# USR_IO_IPMI.net
KiCad netlist of a schematic drawn in Altium Designer
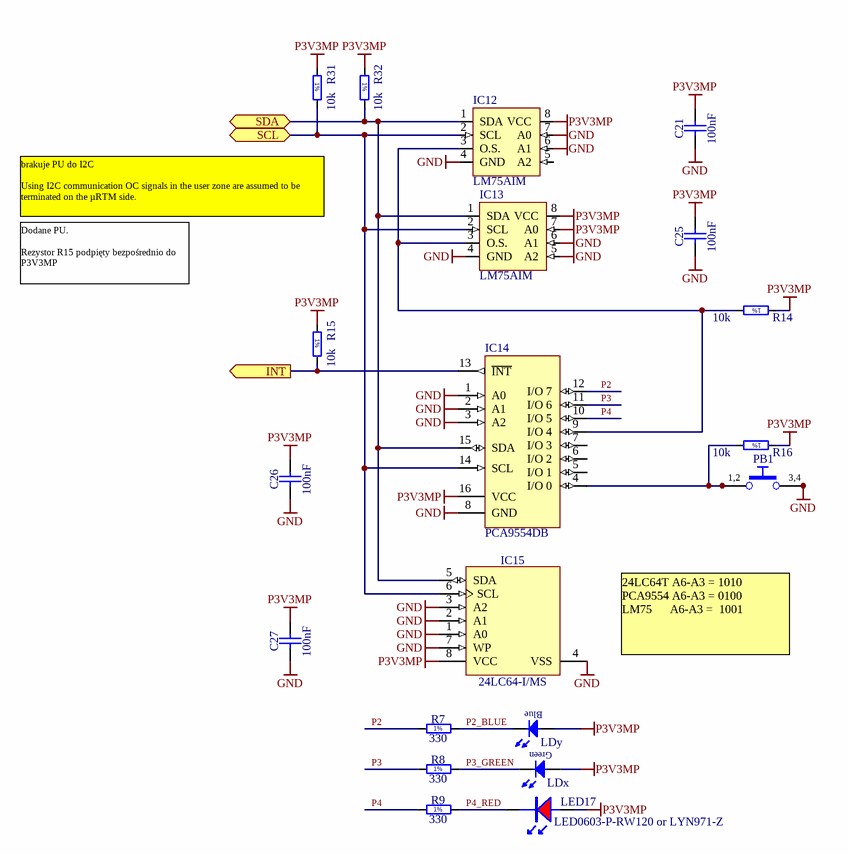
[diagram p0: USR_IO_IPMI.SchDoc]

(export (version "E")
  (design (tool "Eeschema 10.0.6"))
  (components
    (comp (ref "C21")
      (value "100nF")
      (footprint "CAPC1005X55N")
      (description "Non-polarised capacitor")
      (fields
        (field (name "PART NUMBER") "CC0402_100NF_16V_10%_X7R")
        (field (name "VOLTAGE") "16V")
        (field (name "AUTHOR") "CERN DEM JLC")
      )
      (libsource (lib "Capacitors") (part "Capacitor - non polarized"))
    )
    (comp (ref "C25")
      (value "100nF")
      (footprint "CAPC1005X55N")
      (description "Non-polarised capacitor")
      (fields
        (field (name "PART NUMBER") "CC0402_100NF_16V_10%_X7R")
        (field (name "VOLTAGE") "16V")
        (field (name "AUTHOR") "CERN DEM JLC")
      )
      (libsource (lib "Capacitors") (part "Capacitor - non polarized"))
    )
    (comp (ref "C26")
      (value "100nF")
      (footprint "CAPC1005X55N")
      (description "Non-polarised capacitor")
      (fields
        (field (name "PART NUMBER") "CC0402_100NF_16V_10%_X7R")
        (field (name "VOLTAGE") "16V")
        (field (name "AUTHOR") "CERN DEM JLC")
      )
      (libsource (lib "Capacitors") (part "Capacitor - non polarized"))
    )
    (comp (ref "C27")
      (value "100nF")
      (footprint "CAPC1005X55N")
      (description "Non-polarised capacitor")
      (fields
        (field (name "PART NUMBER") "CC0402_100NF_16V_10%_X7R")
        (field (name "VOLTAGE") "16V")
        (field (name "AUTHOR") "CERN DEM JLC")
      )
      (libsource (lib "Capacitors") (part "Capacitor - non polarized"))
    )
    (comp (ref "IC12")
      (value "LM75AIM")
      (footprint "SOIC127P600X175-8N")
      (description "I2C temperature sensor")
      (libsource (lib "LIBRARY_SCH") (part "SENS_LM75"))
    )
    (comp (ref "IC13")
      (value "LM75AIM")
      (footprint "SOIC127P600X175-8N")
      (description "I2C temperature sensor")
      (libsource (lib "LIBRARY_SCH") (part "SENS_LM75"))
    )
    (comp (ref "IC14")
      (value "PCA9554DB")
      (footprint "SOP65P640X120-16N")
      (description "8-bit I2C-bus SMBus I/O port with interrupt")
      (libsource (lib "wr_switch") (part "PCA9554D"))
    )
    (comp (ref "IC15")
      (value "24LC64-I/MS")
      (footprint "SOP65P490X110-8N")
      (description "64K I2C Serial EEPROM")
      (fields (field (name "MANUFACTURER") "MICROCHIP TECHNOLOGY") (field (name "AUTHOR") "CERN DEM JLC"))
      (libsource (lib "ICs And Semiconductors") (part "24LC64-I/MS"))
    )
    (comp (ref "LDx")
      (value "Green")
      (footprint "LED_AVAGO_HSME-C120")
      (description "LED Green Avago C120")
      (fields
        (field (name "PART NUMBER") "LED_AVAGO_HSME-C120")
        (field (name "MANUFACTURER") "AVAGO TECHNOLOGIES")
        (field (name "AUTHOR") "CERN DEM JMW")
      )
      (libsource (lib "LIBRARY_SCH") (part "LED_SMD_90deg_mini_G"))
    )
    (comp (ref "LDy")
      (value "Blue")
      (footprint "LED_AVAGO_HSME-C120")
      (description "LED Blue Avago C120")
      (fields
        (field (name "PART NUMBER") "LED_AVAGO_HSMR-C120")
        (field (name "MANUFACTURER") "AVAGO TECHNOLOGIES")
        (field (name "AUTHOR") "CERN DEM JMW")
      )
      (libsource (lib "LIBRARY_SCH") (part "LED_SMD_90deg_mini_B"))
    )
    (comp (ref "LED17")
      (value "LED0603-P-RW120 or LYN971-Z")
      (footprint "led_0603R")
      (description "LED 0603 red")
      (libsource (lib "LIBRARY_SCH") (part "LED_0603R"))
    )
    (comp (ref "PB1")
      (value "Push Button")
      (footprint "SW_C&K_HDT0001")
      (description "Push-Button Switch SPDT")
      (fields
        (field (name "PART NUMBER") "SW_C&K_HDT0001")
        (field (name "MANUFACTURER") "C&K")
        (field (name "AUTHOR") "CERN DEM JLC")
      )
      (libsource (lib "Eletro-mechanical") (part "PB SPST 12NO-34NO"))
    )
    (comp (ref "R7")
      (value "330")
      (footprint "RESC1608X55N")
      (description "Resistor - 1%")
      (fields
        (field (name "PART NUMBER") "R0603_330R_1%_0.1W_100PPM")
        (field (name "POWER") "0.1W")
        (field (name "AUTHOR") "CERN DEM JLC")
      )
      (libsource (lib "Resistors") (part "Resistor - 1%"))
    )
    (comp (ref "R8")
      (value "330")
      (footprint "RESC1608X55N")
      (description "Resistor - 1%")
      (fields
        (field (name "PART NUMBER") "R0603_330R_1%_0.1W_100PPM")
        (field (name "POWER") "0.1W")
        (field (name "AUTHOR") "CERN DEM JLC")
      )
      (libsource (lib "Resistors") (part "Resistor - 1%"))
    )
    (comp (ref "R9")
      (value "330")
      (footprint "RESC1608X55N")
      (description "Resistor - 1%")
      (fields
        (field (name "PART NUMBER") "R0603_330R_1%_0.1W_100PPM")
        (field (name "POWER") "0.1W")
        (field (name "AUTHOR") "CERN DEM JLC")
      )
      (libsource (lib "Resistors") (part "Resistor - 1%"))
    )
    (comp (ref "R14")
      (value "10k")
      (footprint "RESC1005X40N")
      (description "Resistor - 1%")
      (fields
        (field (name "PART NUMBER") "R0402_10K_1%_0.0625W_100PPM")
        (field (name "POWER") "0.0625W")
        (field (name "AUTHOR") "CERN DEM JLC")
      )
      (libsource (lib "Resistors") (part "Resistor - 1%"))
    )
    (comp (ref "R15")
      (value "10k")
      (footprint "RESC1005X40N")
      (description "Resistor - 1%")
      (fields
        (field (name "PART NUMBER") "R0402_10K_1%_0.0625W_100PPM")
        (field (name "POWER") "0.0625W")
        (field (name "AUTHOR") "CERN DEM JLC")
      )
      (libsource (lib "Resistors") (part "Resistor - 1%"))
    )
    (comp (ref "R16")
      (value "10k")
      (footprint "RESC1005X40N")
      (description "Resistor - 1%")
      (fields
        (field (name "PART NUMBER") "R0402_10K_1%_0.0625W_100PPM")
        (field (name "POWER") "0.0625W")
        (field (name "AUTHOR") "CERN DEM JLC")
      )
      (libsource (lib "Resistors") (part "Resistor - 1%"))
    )
    (comp (ref "R31")
      (value "10k")
      (footprint "RESC1005X40N")
      (description "Resistor - 1%")
      (fields
        (field (name "PART NUMBER") "R0402_10K_1%_0.0625W_100PPM")
        (field (name "POWER") "0.0625W")
        (field (name "AUTHOR") "CERN DEM JLC")
      )
      (libsource (lib "Resistors") (part "Resistor - 1%"))
    )
    (comp (ref "R32")
      (value "10k")
      (footprint "RESC1005X40N")
      (description "Resistor - 1%")
      (fields
        (field (name "PART NUMBER") "R0402_10K_1%_0.0625W_100PPM")
        (field (name "POWER") "0.0625W")
        (field (name "AUTHOR") "CERN DEM JLC")
      )
      (libsource (lib "Resistors") (part "Resistor - 1%"))
    )
  )
  (nets
    (net (code "1") (name "/INT") (class "Default")
      (node (ref "IC14") (pin "13") (pinfunction "~{INT}_13") (pintype "output"))
      (node (ref "R15") (pin "2") (pinfunction "2_2") (pintype "passive"))
    )
    (net (code "2") (name "/P2") (class "Default")
      (node (ref "IC14") (pin "12") (pinfunction "I/O_7_12") (pintype "bidirectional"))
      (node (ref "R7") (pin "1") (pinfunction "1_1") (pintype "passive"))
    )
    (net (code "3") (name "/P2_BLUE") (class "Default")
      (node (ref "LDy") (pin "2") (pinfunction "C_2") (pintype "passive"))
      (node (ref "R7") (pin "2") (pinfunction "2_2") (pintype "passive"))
    )
    (net (code "4") (name "/P3") (class "Default")
      (node (ref "IC14") (pin "11") (pinfunction "I/O_6_11") (pintype "bidirectional"))
      (node (ref "R8") (pin "1") (pinfunction "1_1") (pintype "passive"))
    )
    (net (code "5") (name "/P3_GREEN") (class "Default")
      (node (ref "LDx") (pin "2") (pinfunction "C_2") (pintype "passive"))
      (node (ref "R8") (pin "2") (pinfunction "2_2") (pintype "passive"))
    )
    (net (code "6") (name "/P4") (class "Default")
      (node (ref "IC14") (pin "10") (pinfunction "I/O_5_10") (pintype "bidirectional"))
      (node (ref "R9") (pin "1") (pinfunction "1_1") (pintype "passive"))
    )
    (net (code "7") (name "/P4_RED") (class "Default")
      (node (ref "LED17") (pin "K") (pinfunction "K_K") (pintype "passive"))
      (node (ref "R9") (pin "2") (pinfunction "2_2") (pintype "passive"))
    )
    (net (code "8") (name "/SCL") (class "Default")
      (node (ref "IC12") (pin "2") (pinfunction "SCL_2") (pintype "input"))
      (node (ref "IC13") (pin "2") (pinfunction "SCL_2") (pintype "input"))
      (node (ref "IC14") (pin "14") (pinfunction "SCL_14") (pintype "input"))
      (node (ref "IC15") (pin "6") (pinfunction "SCL_6") (pintype "input"))
      (node (ref "R31") (pin "2") (pinfunction "2_2") (pintype "passive"))
    )
    (net (code "9") (name "/SDA") (class "Default")
      (node (ref "IC12") (pin "1") (pinfunction "SDA_1") (pintype "bidirectional"))
      (node (ref "IC13") (pin "1") (pinfunction "SDA_1") (pintype "bidirectional"))
      (node (ref "IC14") (pin "15") (pinfunction "SDA_15") (pintype "bidirectional"))
      (node (ref "IC15") (pin "5") (pinfunction "SDA_5") (pintype "bidirectional"))
      (node (ref "R32") (pin "2") (pinfunction "2_2") (pintype "passive"))
    )
    (net (code "10") (name "GND") (class "Default")
      (node (ref "C21") (pin "2") (pinfunction "2_2") (pintype "passive"))
      (node (ref "C25") (pin "2") (pinfunction "2_2") (pintype "passive"))
      (node (ref "C26") (pin "2") (pinfunction "2_2") (pintype "passive"))
      (node (ref "C27") (pin "2") (pinfunction "2_2") (pintype "passive"))
      (node (ref "IC12") (pin "4") (pinfunction "GND_4") (pintype "power_in"))
      (node (ref "IC12") (pin "6") (pinfunction "A1_6") (pintype "input"))
      (node (ref "IC12") (pin "7") (pinfunction "A0_7") (pintype "input"))
      (node (ref "IC13") (pin "4") (pinfunction "GND_4") (pintype "power_in"))
      (node (ref "IC13") (pin "5") (pinfunction "A2_5") (pintype "input"))
      (node (ref "IC13") (pin "6") (pinfunction "A1_6") (pintype "input"))
      (node (ref "IC14") (pin "1") (pinfunction "A0_1") (pintype "input"))
      (node (ref "IC14") (pin "2") (pinfunction "A1_2") (pintype "input"))
      (node (ref "IC14") (pin "3") (pinfunction "A2_3") (pintype "input"))
      (node (ref "IC14") (pin "8") (pinfunction "GND_8") (pintype "power_in"))
      (node (ref "IC15") (pin "1") (pinfunction "A0_1") (pintype "input"))
      (node (ref "IC15") (pin "2") (pinfunction "A1_2") (pintype "input"))
      (node (ref "IC15") (pin "3") (pinfunction "A2_3") (pintype "input"))
      (node (ref "IC15") (pin "4") (pinfunction "VSS_4") (pintype "power_in"))
      (node (ref "IC15") (pin "7") (pinfunction "WP_7") (pintype "input"))
      (node (ref "PB1") (pin "3") (pinfunction "3_3") (pintype "passive"))
      (node (ref "PB1") (pin "4") (pinfunction "4_4") (pintype "passive"))
    )
    (net (code "11") (name "Net-(IC12-O.S.)") (class "Default")
      (node (ref "IC12") (pin "3") (pinfunction "O.S._3") (pintype "open_collector"))
      (node (ref "IC13") (pin "3") (pinfunction "O.S._3") (pintype "open_collector"))
      (node (ref "IC14") (pin "9") (pinfunction "I/O_4_9") (pintype "bidirectional"))
      (node (ref "R14") (pin "2") (pinfunction "2_2") (pintype "passive"))
    )
    (net (code "12") (name "Net-(IC14-I{slash}O_0)") (class "Default")
      (node (ref "IC14") (pin "4") (pinfunction "I/O_0_4") (pintype "bidirectional"))
      (node (ref "PB1") (pin "1") (pinfunction "1_1") (pintype "passive"))
      (node (ref "PB1") (pin "2") (pinfunction "2_2") (pintype "passive"))
      (node (ref "R16") (pin "2") (pinfunction "2_2") (pintype "passive"))
    )
    (net (code "13") (name "P3V3MP") (class "Default")
      (node (ref "C21") (pin "1") (pinfunction "1_1") (pintype "passive"))
      (node (ref "C25") (pin "1") (pinfunction "1_1") (pintype "passive"))
      (node (ref "C26") (pin "1") (pinfunction "1_1") (pintype "passive"))
      (node (ref "C27") (pin "1") (pinfunction "1_1") (pintype "passive"))
      (node (ref "IC12") (pin "8") (pinfunction "VCC_8") (pintype "power_in"))
      (node (ref "IC13") (pin "7") (pinfunction "A0_7") (pintype "input"))
      (node (ref "IC13") (pin "8") (pinfunction "VCC_8") (pintype "power_in"))
      (node (ref "IC14") (pin "16") (pinfunction "VCC_16") (pintype "power_in"))
      (node (ref "IC15") (pin "8") (pinfunction "VCC_8") (pintype "power_in"))
      (node (ref "LDx") (pin "1") (pinfunction "A_1") (pintype "passive"))
      (node (ref "LDy") (pin "1") (pinfunction "A_1") (pintype "passive"))
      (node (ref "LED17") (pin "A") (pinfunction "A_A") (pintype "passive"))
      (node (ref "R14") (pin "1") (pinfunction "1_1") (pintype "passive"))
      (node (ref "R15") (pin "1") (pinfunction "1_1") (pintype "passive"))
      (node (ref "R16") (pin "1") (pinfunction "1_1") (pintype "passive"))
      (node (ref "R31") (pin "1") (pinfunction "1_1") (pintype "passive"))
      (node (ref "R32") (pin "1") (pinfunction "1_1") (pintype "passive"))
    )
    (net (code "14") (name "unconnected-(IC12-A2-Pad5)") (class "Default")
      (node (ref "IC12") (pin "5") (pinfunction "A2_5") (pintype "input"))
    )
    (net (code "15") (name "unconnected-(IC14-I{slash}O_1-Pad5)") (class "Default")
      (node (ref "IC14") (pin "5") (pinfunction "I/O_1_5") (pintype "bidirectional"))
    )
    (net (code "16") (name "unconnected-(IC14-I{slash}O_2-Pad6)") (class "Default")
      (node (ref "IC14") (pin "6") (pinfunction "I/O_2_6") (pintype "bidirectional"))
    )
    (net (code "17") (name "unconnected-(IC14-I{slash}O_3-Pad7)") (class "Default")
      (node (ref "IC14") (pin "7") (pinfunction "I/O_3_7") (pintype "bidirectional"))
    )
  )
)
